# led_ppm_display_w_gp.net
KiCad netlist of a schematic drawn in EAGLE
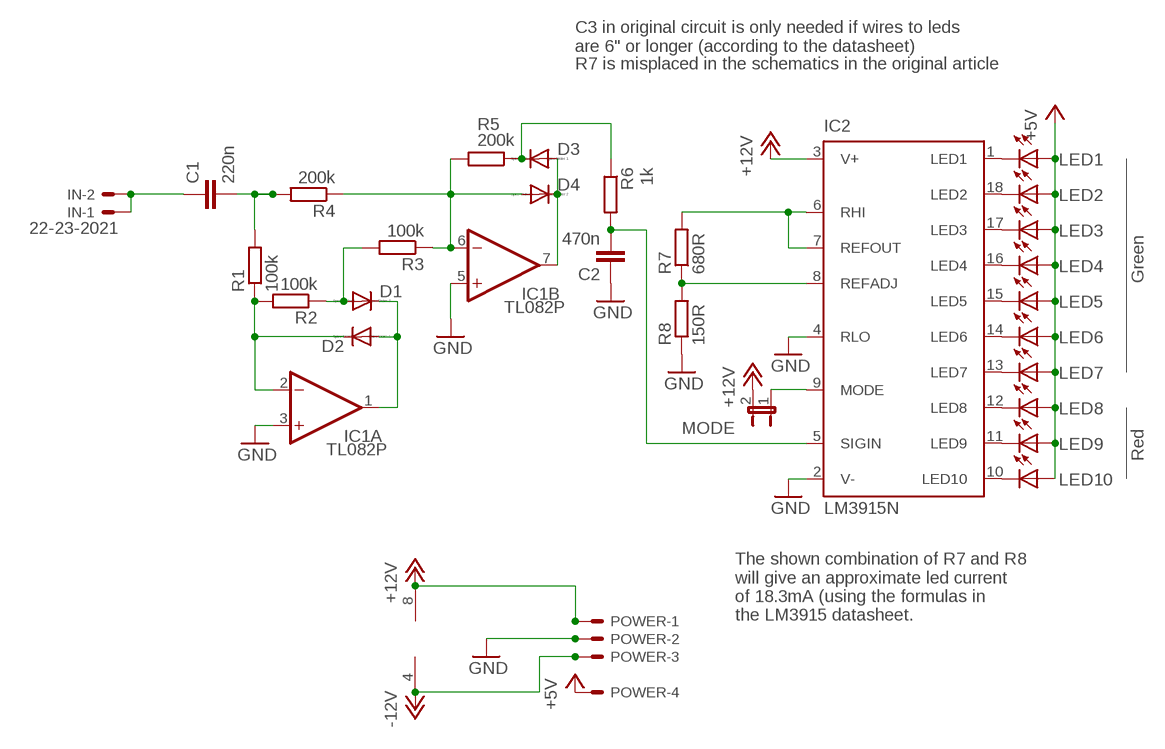
[diagram p0: schematic, sheet 1]

(export (version "E")
  (design (tool "Eeschema 10.0.6"))
  (components
    (comp (ref "C1")
      (value "220n")
      (footprint "eagle-import:C050-025X075")
      (libsource (lib "eagle-import") (part "C-EU050-025X075"))
    )
    (comp (ref "C2")
      (value "470n")
      (footprint "eagle-import:C050-025X075")
      (libsource (lib "eagle-import") (part "C-EU050-025X075"))
    )
    (comp (ref "D1")
      (value "1N4148DOJ35-5")
      (footprint "eagle-import:DO35-5J")
      (libsource (lib "eagle-import") (part "1N4148DOJ35-5"))
    )
    (comp (ref "D2")
      (value "1N4148DOJ35-5")
      (footprint "eagle-import:DO35-5J")
      (libsource (lib "eagle-import") (part "1N4148DOJ35-5"))
    )
    (comp (ref "D3")
      (value "1N4148DOJ35-5")
      (footprint "eagle-import:DO35-5J")
      (libsource (lib "eagle-import") (part "1N4148DOJ35-5"))
    )
    (comp (ref "D4")
      (value "1N4148DOJ35-5")
      (footprint "eagle-import:DO35-5J")
      (libsource (lib "eagle-import") (part "1N4148DOJ35-5"))
    )
    (comp (ref "IC1")
      (value "TL082P")
      (footprint "eagle-import:DIL08")
      (libsource (lib "eagle-import") (part "TL082P"))
    )
    (comp (ref "IC2")
      (value "LM3915N")
      (footprint "eagle-import:DIL18")
      (libsource (lib "eagle-import") (part "LM391N5"))
    )
    (comp (ref "IN")
      (value "22-23-2021")
      (footprint "eagle-import:22-23-2021")
      (fields (field (name "MF") "MOLEX"))
      (libsource (lib "eagle-import") (part "22-23-2021"))
    )
    (comp (ref "LED1")
      (value "LED3MM")
      (footprint "eagle-import:LED3MM")
      (libsource (lib "eagle-import") (part "LED3MM"))
    )
    (comp (ref "LED2")
      (value "LED3MM")
      (footprint "eagle-import:LED3MM")
      (libsource (lib "eagle-import") (part "LED3MM"))
    )
    (comp (ref "LED3")
      (value "LED3MM")
      (footprint "eagle-import:LED3MM")
      (libsource (lib "eagle-import") (part "LED3MM"))
    )
    (comp (ref "LED4")
      (value "LED3MM")
      (footprint "eagle-import:LED3MM")
      (libsource (lib "eagle-import") (part "LED3MM"))
    )
    (comp (ref "LED5")
      (value "LED3MM")
      (footprint "eagle-import:LED3MM")
      (libsource (lib "eagle-import") (part "LED3MM"))
    )
    (comp (ref "LED6")
      (value "LED3MM")
      (footprint "eagle-import:LED3MM")
      (libsource (lib "eagle-import") (part "LED3MM"))
    )
    (comp (ref "LED7")
      (value "LED3MM")
      (footprint "eagle-import:LED3MM")
      (libsource (lib "eagle-import") (part "LED3MM"))
    )
    (comp (ref "LED8")
      (value "LED3MM")
      (footprint "eagle-import:LED3MM")
      (libsource (lib "eagle-import") (part "LED3MM"))
    )
    (comp (ref "LED9")
      (value "LED3MM")
      (footprint "eagle-import:LED3MM")
      (libsource (lib "eagle-import") (part "LED3MM"))
    )
    (comp (ref "LED10")
      (value "LED3MM")
      (footprint "eagle-import:LED3MM")
      (libsource (lib "eagle-import") (part "LED3MM"))
    )
    (comp (ref "MODE")
      (value "JP1E")
      (footprint "eagle-import:JP1")
      (libsource (lib "eagle-import") (part "JP1E"))
    )
    (comp (ref "POWER")
      (value "KK-156-4")
      (footprint "eagle-import:KK-156-4")
      (libsource (lib "eagle-import") (part "KK-156-4"))
    )
    (comp (ref "R1")
      (value "100k")
      (footprint "eagle-import:0207_7")
      (libsource (lib "eagle-import") (part "R-EU_0207/7"))
    )
    (comp (ref "R2")
      (value "100k")
      (footprint "eagle-import:0207_7")
      (libsource (lib "eagle-import") (part "R-EU_0207/7"))
    )
    (comp (ref "R3")
      (value "100k")
      (footprint "eagle-import:0207_7")
      (libsource (lib "eagle-import") (part "R-EU_0207/7"))
    )
    (comp (ref "R4")
      (value "200k")
      (footprint "eagle-import:0207_7")
      (libsource (lib "eagle-import") (part "R-EU_0207/7"))
    )
    (comp (ref "R5")
      (value "200k")
      (footprint "eagle-import:0207_7")
      (libsource (lib "eagle-import") (part "R-EU_0207/7"))
    )
    (comp (ref "R6")
      (value "1k")
      (footprint "eagle-import:0207_7")
      (libsource (lib "eagle-import") (part "R-EU_0207/7"))
    )
    (comp (ref "R7")
      (value "680R")
      (footprint "eagle-import:0207_7")
      (libsource (lib "eagle-import") (part "R-EU_0207/7"))
    )
    (comp (ref "R8")
      (value "150R")
      (footprint "eagle-import:0207_7")
      (libsource (lib "eagle-import") (part "R-EU_0207/7"))
    )
  )
  (nets
    (net (code "1") (name "+5V") (class "Default")
      (node (ref "LED1") (pin "A") (pinfunction "A_A") (pintype "passive"))
      (node (ref "LED10") (pin "A") (pinfunction "A_A") (pintype "passive"))
      (node (ref "LED2") (pin "A") (pinfunction "A_A") (pintype "passive"))
      (node (ref "LED3") (pin "A") (pinfunction "A_A") (pintype "passive"))
      (node (ref "LED4") (pin "A") (pinfunction "A_A") (pintype "passive"))
      (node (ref "LED5") (pin "A") (pinfunction "A_A") (pintype "passive"))
      (node (ref "LED6") (pin "A") (pinfunction "A_A") (pintype "passive"))
      (node (ref "LED7") (pin "A") (pinfunction "A_A") (pintype "passive"))
      (node (ref "LED8") (pin "A") (pinfunction "A_A") (pintype "passive"))
      (node (ref "LED9") (pin "A") (pinfunction "A_A") (pintype "passive"))
      (node (ref "POWER") (pin "4") (pinfunction "S_4") (pintype "passive"))
    )
    (net (code "2") (name "+12V") (class "Default")
      (node (ref "IC1") (pin "8") (pinfunction "V+_8") (pintype "power_in"))
      (node (ref "IC2") (pin "3") (pinfunction "V+_3") (pintype "power_in"))
      (node (ref "MODE") (pin "2") (pinfunction "2_2") (pintype "passive"))
      (node (ref "POWER") (pin "1") (pinfunction "S_1") (pintype "passive"))
    )
    (net (code "3") (name "-12V") (class "Default")
      (node (ref "IC1") (pin "4") (pinfunction "V-_4") (pintype "power_in"))
      (node (ref "POWER") (pin "3") (pinfunction "S_3") (pintype "passive"))
    )
    (net (code "4") (name "GND") (class "Default")
      (node (ref "C2") (pin "1") (pinfunction "1_1") (pintype "passive"))
      (node (ref "IC1") (pin "3") (pinfunction "+IN_3") (pintype "input"))
      (node (ref "IC1") (pin "5") (pinfunction "+IN_5") (pintype "input"))
      (node (ref "IC2") (pin "2") (pinfunction "V-_2") (pintype "power_in"))
      (node (ref "IC2") (pin "4") (pinfunction "RLO_4") (pintype "input"))
      (node (ref "POWER") (pin "2") (pinfunction "S_2") (pintype "passive"))
      (node (ref "R8") (pin "1") (pinfunction "1_1") (pintype "passive"))
    )
    (net (code "5") (name "Net-(C1-Pad2)") (class "Default")
      (node (ref "C1") (pin "2") (pinfunction "2_2") (pintype "passive"))
      (node (ref "R1") (pin "2") (pinfunction "2_2") (pintype "passive"))
      (node (ref "R4") (pin "2") (pinfunction "2_2") (pintype "passive"))
    )
    (net (code "6") (name "Net-(D1-PadA)") (class "Default")
      (node (ref "D1") (pin "A") (pinfunction "A_A") (pintype "passive"))
      (node (ref "R2") (pin "1") (pinfunction "1_1") (pintype "passive"))
      (node (ref "R3") (pin "2") (pinfunction "2_2") (pintype "passive"))
    )
    (net (code "7") (name "Net-(D3-PadC)") (class "Default")
      (node (ref "D3") (pin "C") (pinfunction "C_C") (pintype "passive"))
      (node (ref "R5") (pin "1") (pinfunction "1_1") (pintype "passive"))
      (node (ref "R6") (pin "1") (pinfunction "1_1") (pintype "passive"))
    )
    (net (code "8") (name "Net-(IC1A--IN)") (class "Default")
      (node (ref "D2") (pin "C") (pinfunction "C_C") (pintype "passive"))
      (node (ref "IC1") (pin "2") (pinfunction "-IN_2") (pintype "input"))
      (node (ref "R1") (pin "1") (pinfunction "1_1") (pintype "passive"))
      (node (ref "R2") (pin "2") (pinfunction "2_2") (pintype "passive"))
    )
    (net (code "9") (name "Net-(IC1A-OUT)") (class "Default")
      (node (ref "D1") (pin "C") (pinfunction "C_C") (pintype "passive"))
      (node (ref "D2") (pin "A") (pinfunction "A_A") (pintype "passive"))
      (node (ref "IC1") (pin "1") (pinfunction "OUT_1") (pintype "output"))
    )
    (net (code "10") (name "Net-(IC1B--IN)") (class "Default")
      (node (ref "D4") (pin "A") (pinfunction "A_A") (pintype "passive"))
      (node (ref "IC1") (pin "6") (pinfunction "-IN_6") (pintype "input"))
      (node (ref "R3") (pin "1") (pinfunction "1_1") (pintype "passive"))
      (node (ref "R4") (pin "1") (pinfunction "1_1") (pintype "passive"))
      (node (ref "R5") (pin "2") (pinfunction "2_2") (pintype "passive"))
    )
    (net (code "11") (name "Net-(IC1B-OUT)") (class "Default")
      (node (ref "D3") (pin "A") (pinfunction "A_A") (pintype "passive"))
      (node (ref "D4") (pin "C") (pinfunction "C_C") (pintype "passive"))
      (node (ref "IC1") (pin "7") (pinfunction "OUT_7") (pintype "output"))
    )
    (net (code "12") (name "Net-(IC2-LED1)") (class "Default")
      (node (ref "IC2") (pin "1") (pinfunction "LED1_1") (pintype "output"))
      (node (ref "LED1") (pin "K") (pinfunction "C_K") (pintype "passive"))
    )
    (net (code "13") (name "Net-(IC2-LED2)") (class "Default")
      (node (ref "IC2") (pin "18") (pinfunction "LED2_18") (pintype "output"))
      (node (ref "LED2") (pin "K") (pinfunction "C_K") (pintype "passive"))
    )
    (net (code "14") (name "Net-(IC2-LED3)") (class "Default")
      (node (ref "IC2") (pin "17") (pinfunction "LED3_17") (pintype "output"))
      (node (ref "LED3") (pin "K") (pinfunction "C_K") (pintype "passive"))
    )
    (net (code "15") (name "Net-(IC2-LED4)") (class "Default")
      (node (ref "IC2") (pin "16") (pinfunction "LED4_16") (pintype "output"))
      (node (ref "LED4") (pin "K") (pinfunction "C_K") (pintype "passive"))
    )
    (net (code "16") (name "Net-(IC2-LED5)") (class "Default")
      (node (ref "IC2") (pin "15") (pinfunction "LED5_15") (pintype "output"))
      (node (ref "LED5") (pin "K") (pinfunction "C_K") (pintype "passive"))
    )
    (net (code "17") (name "Net-(IC2-LED6)") (class "Default")
      (node (ref "IC2") (pin "14") (pinfunction "LED6_14") (pintype "output"))
      (node (ref "LED6") (pin "K") (pinfunction "C_K") (pintype "passive"))
    )
    (net (code "18") (name "Net-(IC2-LED7)") (class "Default")
      (node (ref "IC2") (pin "13") (pinfunction "LED7_13") (pintype "output"))
      (node (ref "LED7") (pin "K") (pinfunction "C_K") (pintype "passive"))
    )
    (net (code "19") (name "Net-(IC2-LED8)") (class "Default")
      (node (ref "IC2") (pin "12") (pinfunction "LED8_12") (pintype "output"))
      (node (ref "LED8") (pin "K") (pinfunction "C_K") (pintype "passive"))
    )
    (net (code "20") (name "Net-(IC2-LED9)") (class "Default")
      (node (ref "IC2") (pin "11") (pinfunction "LED9_11") (pintype "output"))
      (node (ref "LED9") (pin "K") (pinfunction "C_K") (pintype "passive"))
    )
    (net (code "21") (name "Net-(IC2-LED10)") (class "Default")
      (node (ref "IC2") (pin "10") (pinfunction "LED10_10") (pintype "output"))
      (node (ref "LED10") (pin "K") (pinfunction "C_K") (pintype "passive"))
    )
    (net (code "22") (name "Net-(IC2-MODE)") (class "Default")
      (node (ref "IC2") (pin "9") (pinfunction "MODE_9") (pintype "input"))
      (node (ref "MODE") (pin "1") (pinfunction "1_1") (pintype "passive"))
    )
    (net (code "23") (name "Net-(IC2-REFADJ)") (class "Default")
      (node (ref "IC2") (pin "8") (pinfunction "REFADJ_8") (pintype "passive"))
      (node (ref "R7") (pin "1") (pinfunction "1_1") (pintype "passive"))
      (node (ref "R8") (pin "2") (pinfunction "2_2") (pintype "passive"))
    )
    (net (code "24") (name "Net-(IC2-REFOUT)") (class "Default")
      (node (ref "IC2") (pin "6") (pinfunction "RHI_6") (pintype "input"))
      (node (ref "IC2") (pin "7") (pinfunction "REFOUT_7") (pintype "output"))
      (node (ref "R7") (pin "2") (pinfunction "2_2") (pintype "passive"))
    )
    (net (code "25") (name "Net-(IC2-SIGIN)") (class "Default")
      (node (ref "C2") (pin "2") (pinfunction "2_2") (pintype "passive"))
      (node (ref "IC2") (pin "5") (pinfunction "SIGIN_5") (pintype "input"))
      (node (ref "R6") (pin "2") (pinfunction "2_2") (pintype "passive"))
    )
    (net (code "26") (name "Net-(INA-S)") (class "Default")
      (node (ref "C1") (pin "1") (pinfunction "1_1") (pintype "passive"))
      (node (ref "IN") (pin "1") (pinfunction "S_1") (pintype "passive"))
      (node (ref "IN") (pin "2") (pinfunction "S_2") (pintype "passive"))
    )
  )
)
